# axiom_beta_plugin_module_3xPMOD_v1_2_22e.net
KiCad netlist of a schematic drawn in EAGLE
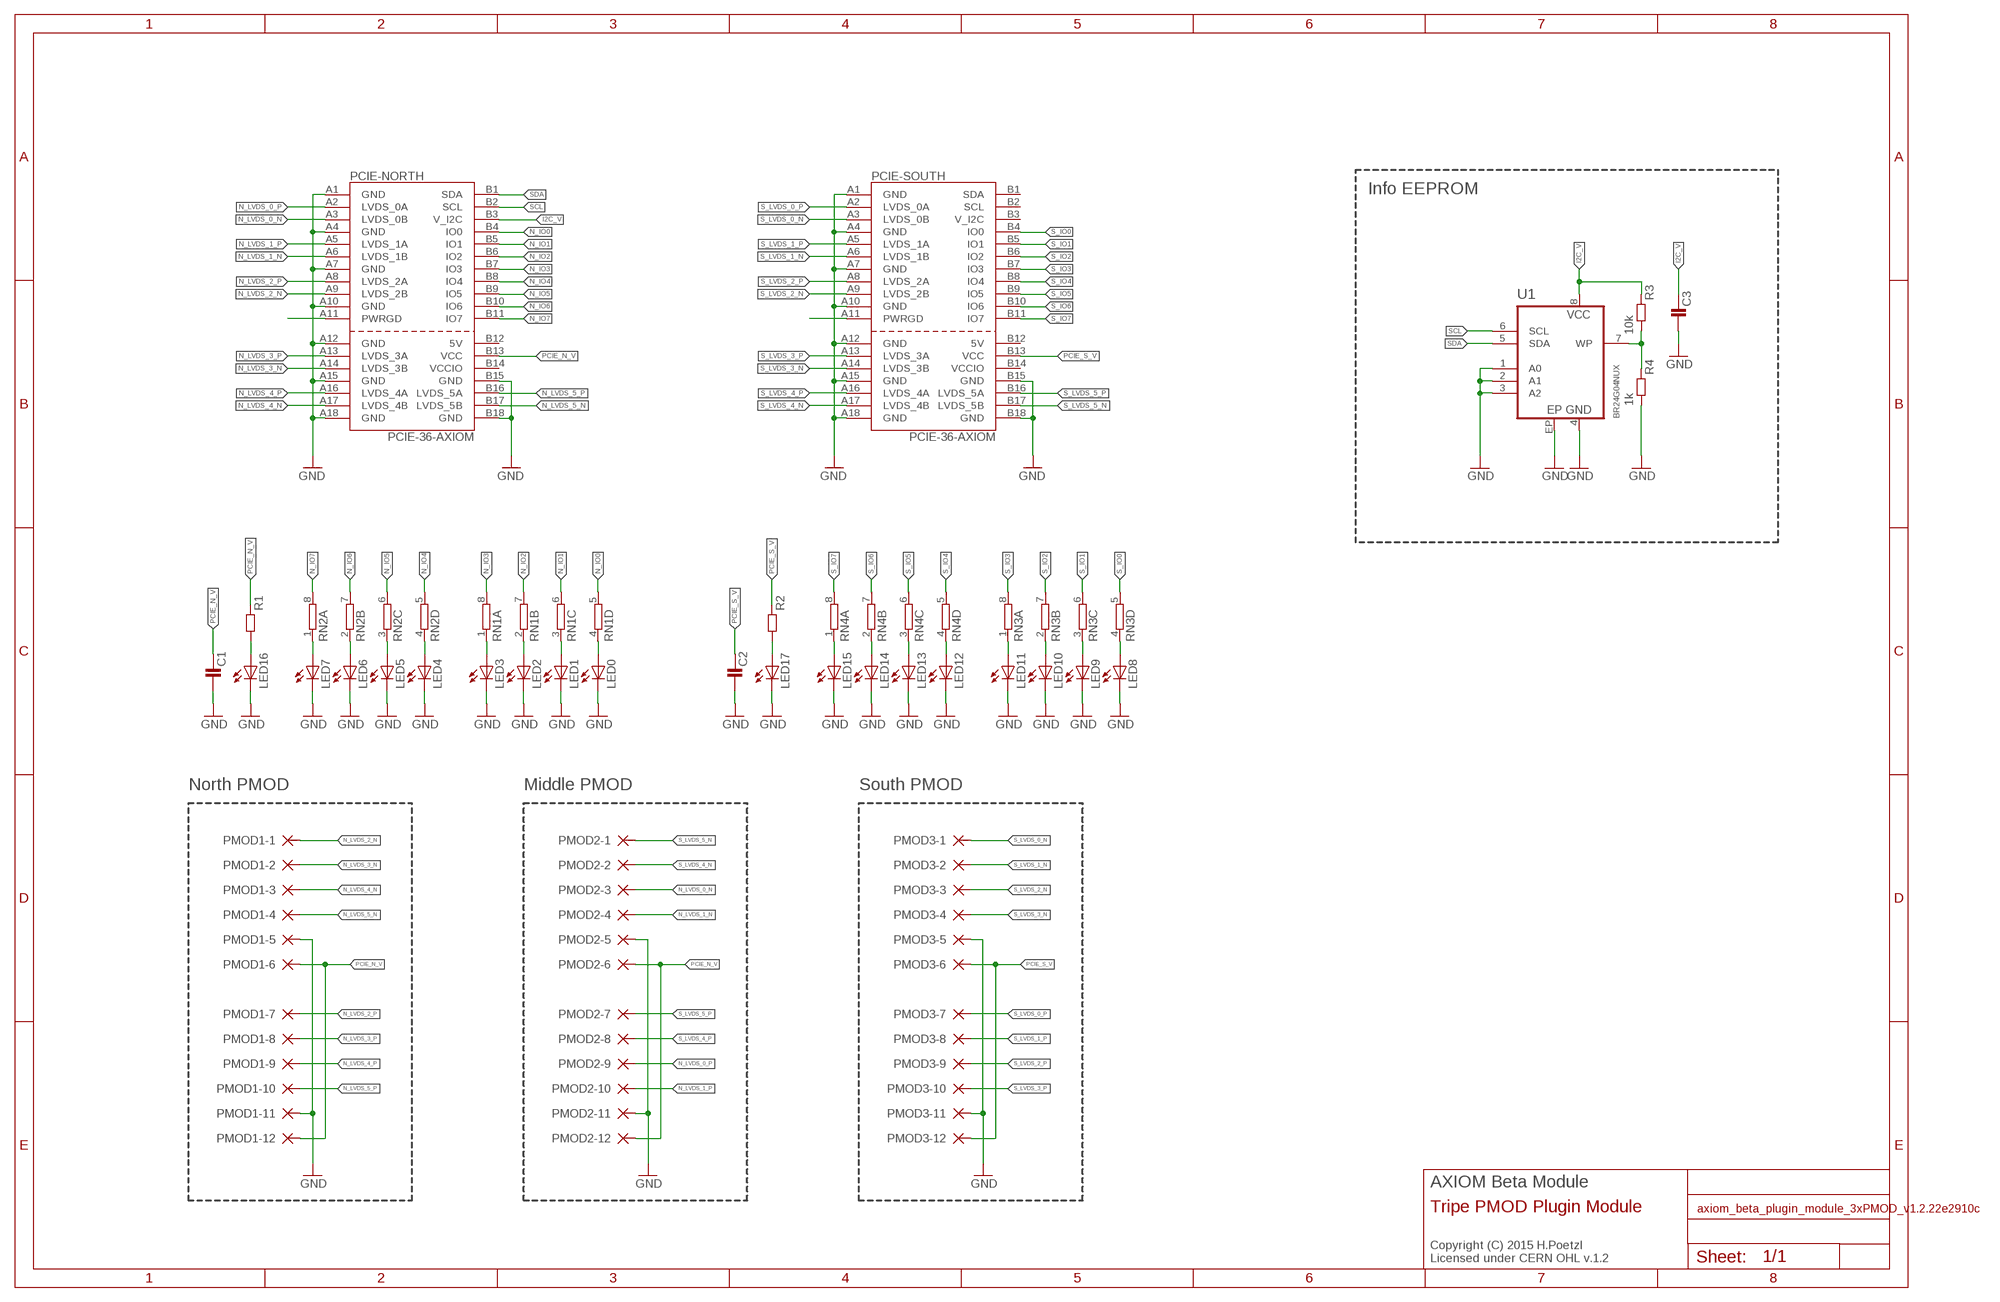
[diagram p0: schematic, sheet 1]

(export (version "E")
  (design (tool "Eeschema 10.0.6"))
  (components
    (comp (ref "C1")
      (value "C1206-A")
      (footprint "eagle-import:1206-A")
      (libsource (lib "eagle-import") (part "C1206-A"))
    )
    (comp (ref "C2")
      (value "C1206-A")
      (footprint "eagle-import:1206-A")
      (libsource (lib "eagle-import") (part "C1206-A"))
    )
    (comp (ref "C3")
      (value "C0402-B")
      (footprint "eagle-import:0402-B")
      (libsource (lib "eagle-import") (part "C0402-B"))
    )
    (comp (ref "LED0")
      (value "LEDCHIPLED_0603")
      (footprint "eagle-import:CHIPLED_0603")
      (libsource (lib "eagle-import") (part "LEDCHIPLED_0603"))
    )
    (comp (ref "LED1")
      (value "LEDCHIPLED_0603")
      (footprint "eagle-import:CHIPLED_0603")
      (libsource (lib "eagle-import") (part "LEDCHIPLED_0603"))
    )
    (comp (ref "LED2")
      (value "LEDCHIPLED_0603")
      (footprint "eagle-import:CHIPLED_0603")
      (libsource (lib "eagle-import") (part "LEDCHIPLED_0603"))
    )
    (comp (ref "LED3")
      (value "LEDCHIPLED_0603")
      (footprint "eagle-import:CHIPLED_0603")
      (libsource (lib "eagle-import") (part "LEDCHIPLED_0603"))
    )
    (comp (ref "LED4")
      (value "LEDCHIPLED_0603")
      (footprint "eagle-import:CHIPLED_0603")
      (libsource (lib "eagle-import") (part "LEDCHIPLED_0603"))
    )
    (comp (ref "LED5")
      (value "LEDCHIPLED_0603")
      (footprint "eagle-import:CHIPLED_0603")
      (libsource (lib "eagle-import") (part "LEDCHIPLED_0603"))
    )
    (comp (ref "LED6")
      (value "LEDCHIPLED_0603")
      (footprint "eagle-import:CHIPLED_0603")
      (libsource (lib "eagle-import") (part "LEDCHIPLED_0603"))
    )
    (comp (ref "LED7")
      (value "LEDCHIPLED_0603")
      (footprint "eagle-import:CHIPLED_0603")
      (libsource (lib "eagle-import") (part "LEDCHIPLED_0603"))
    )
    (comp (ref "LED8")
      (value "LEDCHIPLED_0603")
      (footprint "eagle-import:CHIPLED_0603")
      (libsource (lib "eagle-import") (part "LEDCHIPLED_0603"))
    )
    (comp (ref "LED9")
      (value "LEDCHIPLED_0603")
      (footprint "eagle-import:CHIPLED_0603")
      (libsource (lib "eagle-import") (part "LEDCHIPLED_0603"))
    )
    (comp (ref "LED10")
      (value "LEDCHIPLED_0603")
      (footprint "eagle-import:CHIPLED_0603")
      (libsource (lib "eagle-import") (part "LEDCHIPLED_0603"))
    )
    (comp (ref "LED11")
      (value "LEDCHIPLED_0603")
      (footprint "eagle-import:CHIPLED_0603")
      (libsource (lib "eagle-import") (part "LEDCHIPLED_0603"))
    )
    (comp (ref "LED12")
      (value "LEDCHIPLED_0603")
      (footprint "eagle-import:CHIPLED_0603")
      (libsource (lib "eagle-import") (part "LEDCHIPLED_0603"))
    )
    (comp (ref "LED13")
      (value "LEDCHIPLED_0603")
      (footprint "eagle-import:CHIPLED_0603")
      (libsource (lib "eagle-import") (part "LEDCHIPLED_0603"))
    )
    (comp (ref "LED14")
      (value "LEDCHIPLED_0603")
      (footprint "eagle-import:CHIPLED_0603")
      (libsource (lib "eagle-import") (part "LEDCHIPLED_0603"))
    )
    (comp (ref "LED15")
      (value "LEDCHIPLED_0603")
      (footprint "eagle-import:CHIPLED_0603")
      (libsource (lib "eagle-import") (part "LEDCHIPLED_0603"))
    )
    (comp (ref "LED16")
      (value "LEDCHIPLED_0603")
      (footprint "eagle-import:CHIPLED_0603")
      (libsource (lib "eagle-import") (part "LEDCHIPLED_0603"))
    )
    (comp (ref "LED17")
      (value "LEDCHIPLED_0603")
      (footprint "eagle-import:CHIPLED_0603")
      (libsource (lib "eagle-import") (part "LEDCHIPLED_0603"))
    )
    (comp (ref "PCIE-NORTH")
      (value "PCIE-36-AXIOM")
      (footprint "eagle-import:PCIE-36-AXIOM")
      (libsource (lib "eagle-import") (part "PCIE-36-AXIOM"))
    )
    (comp (ref "PCIE-SOUTH")
      (value "PCIE-36-AXIOM")
      (footprint "eagle-import:PCIE-36-AXIOM")
      (libsource (lib "eagle-import") (part "PCIE-36-AXIOM"))
    )
    (comp (ref "PMOD1-1")
      (value "SMD-PAD1.6X3.8MM-U")
      (footprint "eagle-import:1.6X3.8U-MM")
      (libsource (lib "eagle-import") (part "SMD-PAD1.6X3.8MM-U"))
    )
    (comp (ref "PMOD1-2")
      (value "SMD-PAD1.6X3.8MM-U")
      (footprint "eagle-import:1.6X3.8U-MM")
      (libsource (lib "eagle-import") (part "SMD-PAD1.6X3.8MM-U"))
    )
    (comp (ref "PMOD1-3")
      (value "SMD-PAD1.6X3.8MM-U")
      (footprint "eagle-import:1.6X3.8U-MM")
      (libsource (lib "eagle-import") (part "SMD-PAD1.6X3.8MM-U"))
    )
    (comp (ref "PMOD1-4")
      (value "SMD-PAD1.6X3.8MM-U")
      (footprint "eagle-import:1.6X3.8U-MM")
      (libsource (lib "eagle-import") (part "SMD-PAD1.6X3.8MM-U"))
    )
    (comp (ref "PMOD1-5")
      (value "SMD-PAD1.6X3.8MM-U")
      (footprint "eagle-import:1.6X3.8U-MM")
      (libsource (lib "eagle-import") (part "SMD-PAD1.6X3.8MM-U"))
    )
    (comp (ref "PMOD1-6")
      (value "SMD-PAD1.6X3.8MM-U")
      (footprint "eagle-import:1.6X3.8U-MM")
      (libsource (lib "eagle-import") (part "SMD-PAD1.6X3.8MM-U"))
    )
    (comp (ref "PMOD1-7")
      (value "SMD-PAD1.6X3.8MM-U")
      (footprint "eagle-import:1.6X3.8U-MM")
      (libsource (lib "eagle-import") (part "SMD-PAD1.6X3.8MM-U"))
    )
    (comp (ref "PMOD1-8")
      (value "SMD-PAD1.6X3.8MM-U")
      (footprint "eagle-import:1.6X3.8U-MM")
      (libsource (lib "eagle-import") (part "SMD-PAD1.6X3.8MM-U"))
    )
    (comp (ref "PMOD1-9")
      (value "SMD-PAD1.6X3.8MM-U")
      (footprint "eagle-import:1.6X3.8U-MM")
      (libsource (lib "eagle-import") (part "SMD-PAD1.6X3.8MM-U"))
    )
    (comp (ref "PMOD1-10")
      (value "SMD-PAD1.6X3.8MM-U")
      (footprint "eagle-import:1.6X3.8U-MM")
      (libsource (lib "eagle-import") (part "SMD-PAD1.6X3.8MM-U"))
    )
    (comp (ref "PMOD1-11")
      (value "SMD-PAD1.6X3.8MM-U")
      (footprint "eagle-import:1.6X3.8U-MM")
      (libsource (lib "eagle-import") (part "SMD-PAD1.6X3.8MM-U"))
    )
    (comp (ref "PMOD1-12")
      (value "SMD-PAD1.6X3.8MM-U")
      (footprint "eagle-import:1.6X3.8U-MM")
      (libsource (lib "eagle-import") (part "SMD-PAD1.6X3.8MM-U"))
    )
    (comp (ref "PMOD2-1")
      (value "SMD-PAD1.6X3.8MM-U")
      (footprint "eagle-import:1.6X3.8U-MM")
      (libsource (lib "eagle-import") (part "SMD-PAD1.6X3.8MM-U"))
    )
    (comp (ref "PMOD2-2")
      (value "SMD-PAD1.6X3.8MM-U")
      (footprint "eagle-import:1.6X3.8U-MM")
      (libsource (lib "eagle-import") (part "SMD-PAD1.6X3.8MM-U"))
    )
    (comp (ref "PMOD2-3")
      (value "SMD-PAD1.6X3.8MM-U")
      (footprint "eagle-import:1.6X3.8U-MM")
      (libsource (lib "eagle-import") (part "SMD-PAD1.6X3.8MM-U"))
    )
    (comp (ref "PMOD2-4")
      (value "SMD-PAD1.6X3.8MM-U")
      (footprint "eagle-import:1.6X3.8U-MM")
      (libsource (lib "eagle-import") (part "SMD-PAD1.6X3.8MM-U"))
    )
    (comp (ref "PMOD2-5")
      (value "SMD-PAD1.6X3.8MM-U")
      (footprint "eagle-import:1.6X3.8U-MM")
      (libsource (lib "eagle-import") (part "SMD-PAD1.6X3.8MM-U"))
    )
    (comp (ref "PMOD2-6")
      (value "SMD-PAD1.6X3.8MM-U")
      (footprint "eagle-import:1.6X3.8U-MM")
      (libsource (lib "eagle-import") (part "SMD-PAD1.6X3.8MM-U"))
    )
    (comp (ref "PMOD2-7")
      (value "SMD-PAD1.6X3.8MM-U")
      (footprint "eagle-import:1.6X3.8U-MM")
      (libsource (lib "eagle-import") (part "SMD-PAD1.6X3.8MM-U"))
    )
    (comp (ref "PMOD2-8")
      (value "SMD-PAD1.6X3.8MM-U")
      (footprint "eagle-import:1.6X3.8U-MM")
      (libsource (lib "eagle-import") (part "SMD-PAD1.6X3.8MM-U"))
    )
    (comp (ref "PMOD2-9")
      (value "SMD-PAD1.6X3.8MM-U")
      (footprint "eagle-import:1.6X3.8U-MM")
      (libsource (lib "eagle-import") (part "SMD-PAD1.6X3.8MM-U"))
    )
    (comp (ref "PMOD2-10")
      (value "SMD-PAD1.6X3.8MM-U")
      (footprint "eagle-import:1.6X3.8U-MM")
      (libsource (lib "eagle-import") (part "SMD-PAD1.6X3.8MM-U"))
    )
    (comp (ref "PMOD2-11")
      (value "SMD-PAD1.6X3.8MM-U")
      (footprint "eagle-import:1.6X3.8U-MM")
      (libsource (lib "eagle-import") (part "SMD-PAD1.6X3.8MM-U"))
    )
    (comp (ref "PMOD2-12")
      (value "SMD-PAD1.6X3.8MM-U")
      (footprint "eagle-import:1.6X3.8U-MM")
      (libsource (lib "eagle-import") (part "SMD-PAD1.6X3.8MM-U"))
    )
    (comp (ref "PMOD3-1")
      (value "SMD-PAD1.6X3.8MM-U")
      (footprint "eagle-import:1.6X3.8U-MM")
      (libsource (lib "eagle-import") (part "SMD-PAD1.6X3.8MM-U"))
    )
    (comp (ref "PMOD3-2")
      (value "SMD-PAD1.6X3.8MM-U")
      (footprint "eagle-import:1.6X3.8U-MM")
      (libsource (lib "eagle-import") (part "SMD-PAD1.6X3.8MM-U"))
    )
    (comp (ref "PMOD3-3")
      (value "SMD-PAD1.6X3.8MM-U")
      (footprint "eagle-import:1.6X3.8U-MM")
      (libsource (lib "eagle-import") (part "SMD-PAD1.6X3.8MM-U"))
    )
    (comp (ref "PMOD3-4")
      (value "SMD-PAD1.6X3.8MM-U")
      (footprint "eagle-import:1.6X3.8U-MM")
      (libsource (lib "eagle-import") (part "SMD-PAD1.6X3.8MM-U"))
    )
    (comp (ref "PMOD3-5")
      (value "SMD-PAD1.6X3.8MM-U")
      (footprint "eagle-import:1.6X3.8U-MM")
      (libsource (lib "eagle-import") (part "SMD-PAD1.6X3.8MM-U"))
    )
    (comp (ref "PMOD3-6")
      (value "SMD-PAD1.6X3.8MM-U")
      (footprint "eagle-import:1.6X3.8U-MM")
      (libsource (lib "eagle-import") (part "SMD-PAD1.6X3.8MM-U"))
    )
    (comp (ref "PMOD3-7")
      (value "SMD-PAD1.6X3.8MM-U")
      (footprint "eagle-import:1.6X3.8U-MM")
      (libsource (lib "eagle-import") (part "SMD-PAD1.6X3.8MM-U"))
    )
    (comp (ref "PMOD3-8")
      (value "SMD-PAD1.6X3.8MM-U")
      (footprint "eagle-import:1.6X3.8U-MM")
      (libsource (lib "eagle-import") (part "SMD-PAD1.6X3.8MM-U"))
    )
    (comp (ref "PMOD3-9")
      (value "SMD-PAD1.6X3.8MM-U")
      (footprint "eagle-import:1.6X3.8U-MM")
      (libsource (lib "eagle-import") (part "SMD-PAD1.6X3.8MM-U"))
    )
    (comp (ref "PMOD3-10")
      (value "SMD-PAD1.6X3.8MM-U")
      (footprint "eagle-import:1.6X3.8U-MM")
      (libsource (lib "eagle-import") (part "SMD-PAD1.6X3.8MM-U"))
    )
    (comp (ref "PMOD3-11")
      (value "SMD-PAD1.6X3.8MM-U")
      (footprint "eagle-import:1.6X3.8U-MM")
      (libsource (lib "eagle-import") (part "SMD-PAD1.6X3.8MM-U"))
    )
    (comp (ref "PMOD3-12")
      (value "SMD-PAD1.6X3.8MM-U")
      (footprint "eagle-import:1.6X3.8U-MM")
      (libsource (lib "eagle-import") (part "SMD-PAD1.6X3.8MM-U"))
    )
    (comp (ref "R1")
      (value "R0402-B")
      (footprint "eagle-import:0402-B")
      (libsource (lib "eagle-import") (part "R0402-B"))
    )
    (comp (ref "R2")
      (value "R0402-B")
      (footprint "eagle-import:0402-B")
      (libsource (lib "eagle-import") (part "R0402-B"))
    )
    (comp (ref "R3")
      (value "10k")
      (footprint "eagle-import:0402-B")
      (libsource (lib "eagle-import") (part "R0402-B"))
    )
    (comp (ref "R4")
      (value "1k")
      (footprint "eagle-import:0402-B")
      (libsource (lib "eagle-import") (part "R0402-B"))
    )
    (comp (ref "RN1")
      (value "4R-NCAY16")
      (footprint "eagle-import:CAY16")
      (libsource (lib "eagle-import") (part "4R-NCAY16"))
    )
    (comp (ref "RN2")
      (value "4R-NCAY16")
      (footprint "eagle-import:CAY16")
      (libsource (lib "eagle-import") (part "4R-NCAY16"))
    )
    (comp (ref "RN3")
      (value "4R-NCAY16")
      (footprint "eagle-import:CAY16")
      (libsource (lib "eagle-import") (part "4R-NCAY16"))
    )
    (comp (ref "RN4")
      (value "4R-NCAY16")
      (footprint "eagle-import:CAY16")
      (libsource (lib "eagle-import") (part "4R-NCAY16"))
    )
    (comp (ref "U1")
      (value "BR24G04NUX")
      (footprint "eagle-import:DFN200X300X100-9N")
      (libsource (lib "eagle-import") (part "BR24G04NUX"))
    )
  )
  (nets
    (net (code "1") (name "GND") (class "Default")
      (node (ref "C1") (pin "2") (pinfunction "2_2") (pintype "passive"))
      (node (ref "C2") (pin "2") (pinfunction "2_2") (pintype "passive"))
      (node (ref "C3") (pin "2") (pinfunction "2_2") (pintype "passive"))
      (node (ref "LED0") (pin "C") (pinfunction "C_C") (pintype "passive"))
      (node (ref "LED1") (pin "C") (pinfunction "C_C") (pintype "passive"))
      (node (ref "LED10") (pin "C") (pinfunction "C_C") (pintype "passive"))
      (node (ref "LED11") (pin "C") (pinfunction "C_C") (pintype "passive"))
      (node (ref "LED12") (pin "C") (pinfunction "C_C") (pintype "passive"))
      (node (ref "LED13") (pin "C") (pinfunction "C_C") (pintype "passive"))
      (node (ref "LED14") (pin "C") (pinfunction "C_C") (pintype "passive"))
      (node (ref "LED15") (pin "C") (pinfunction "C_C") (pintype "passive"))
      (node (ref "LED16") (pin "C") (pinfunction "C_C") (pintype "passive"))
      (node (ref "LED17") (pin "C") (pinfunction "C_C") (pintype "passive"))
      (node (ref "LED2") (pin "C") (pinfunction "C_C") (pintype "passive"))
      (node (ref "LED3") (pin "C") (pinfunction "C_C") (pintype "passive"))
      (node (ref "LED4") (pin "C") (pinfunction "C_C") (pintype "passive"))
      (node (ref "LED5") (pin "C") (pinfunction "C_C") (pintype "passive"))
      (node (ref "LED6") (pin "C") (pinfunction "C_C") (pintype "passive"))
      (node (ref "LED7") (pin "C") (pinfunction "C_C") (pintype "passive"))
      (node (ref "LED8") (pin "C") (pinfunction "C_C") (pintype "passive"))
      (node (ref "LED9") (pin "C") (pinfunction "C_C") (pintype "passive"))
      (node (ref "PCIE-NORTH") (pin "A1") (pinfunction "GND_A1") (pintype "passive"))
      (node (ref "PCIE-NORTH") (pin "A10") (pinfunction "GND_A10") (pintype "passive"))
      (node (ref "PCIE-NORTH") (pin "A12") (pinfunction "GND_A12") (pintype "passive"))
      (node (ref "PCIE-NORTH") (pin "A15") (pinfunction "GND_A15") (pintype "passive"))
      (node (ref "PCIE-NORTH") (pin "A18") (pinfunction "GND_A18") (pintype "passive"))
      (node (ref "PCIE-NORTH") (pin "A4") (pinfunction "GND_A4") (pintype "passive"))
      (node (ref "PCIE-NORTH") (pin "A7") (pinfunction "GND_A7") (pintype "passive"))
      (node (ref "PCIE-NORTH") (pin "B15") (pinfunction "GND_B15") (pintype "passive"))
      (node (ref "PCIE-NORTH") (pin "B18") (pinfunction "GND_B18") (pintype "passive"))
      (node (ref "PCIE-SOUTH") (pin "A1") (pinfunction "GND_A1") (pintype "passive"))
      (node (ref "PCIE-SOUTH") (pin "A10") (pinfunction "GND_A10") (pintype "passive"))
      (node (ref "PCIE-SOUTH") (pin "A12") (pinfunction "GND_A12") (pintype "passive"))
      (node (ref "PCIE-SOUTH") (pin "A15") (pinfunction "GND_A15") (pintype "passive"))
      (node (ref "PCIE-SOUTH") (pin "A18") (pinfunction "GND_A18") (pintype "passive"))
      (node (ref "PCIE-SOUTH") (pin "A4") (pinfunction "GND_A4") (pintype "passive"))
      (node (ref "PCIE-SOUTH") (pin "A7") (pinfunction "GND_A7") (pintype "passive"))
      (node (ref "PCIE-SOUTH") (pin "B15") (pinfunction "GND_B15") (pintype "passive"))
      (node (ref "PCIE-SOUTH") (pin "B18") (pinfunction "GND_B18") (pintype "passive"))
      (node (ref "PMOD1-11") (pin "1") (pinfunction "P_1") (pintype "passive"))
      (node (ref "PMOD1-5") (pin "1") (pinfunction "P_1") (pintype "passive"))
      (node (ref "PMOD2-11") (pin "1") (pinfunction "P_1") (pintype "passive"))
      (node (ref "PMOD2-5") (pin "1") (pinfunction "P_1") (pintype "passive"))
      (node (ref "PMOD3-11") (pin "1") (pinfunction "P_1") (pintype "passive"))
      (node (ref "PMOD3-5") (pin "1") (pinfunction "P_1") (pintype "passive"))
      (node (ref "R4") (pin "2") (pinfunction "2_2") (pintype "passive"))
      (node (ref "U1") (pin "1") (pinfunction "A0_1") (pintype "input"))
      (node (ref "U1") (pin "2") (pinfunction "A1_2") (pintype "input"))
      (node (ref "U1") (pin "3") (pinfunction "A2_3") (pintype "input"))
      (node (ref "U1") (pin "4") (pinfunction "GND_4") (pintype "passive"))
      (node (ref "U1") (pin "EP") (pinfunction "EP_EP") (pintype "passive"))
    )
    (net (code "2") (name "I2C_V") (class "Default")
      (node (ref "C3") (pin "1") (pinfunction "1_1") (pintype "passive"))
      (node (ref "PCIE-NORTH") (pin "B3") (pinfunction "V_I2C_B3") (pintype "passive"))
      (node (ref "R3") (pin "1") (pinfunction "1_1") (pintype "passive"))
      (node (ref "U1") (pin "8") (pinfunction "VCC_8") (pintype "power_in"))
    )
    (net (code "3") (name "N_IO0") (class "Default")
      (node (ref "PCIE-NORTH") (pin "B4") (pinfunction "IO0_B4") (pintype "passive"))
      (node (ref "RN1") (pin "5") (pinfunction "2_5") (pintype "passive"))
    )
    (net (code "4") (name "N_IO1") (class "Default")
      (node (ref "PCIE-NORTH") (pin "B5") (pinfunction "IO1_B5") (pintype "passive"))
      (node (ref "RN1") (pin "6") (pinfunction "2_6") (pintype "passive"))
    )
    (net (code "5") (name "N_IO2") (class "Default")
      (node (ref "PCIE-NORTH") (pin "B6") (pinfunction "IO2_B6") (pintype "passive"))
      (node (ref "RN1") (pin "7") (pinfunction "2_7") (pintype "passive"))
    )
    (net (code "6") (name "N_IO3") (class "Default")
      (node (ref "PCIE-NORTH") (pin "B7") (pinfunction "IO3_B7") (pintype "passive"))
      (node (ref "RN1") (pin "8") (pinfunction "2_8") (pintype "passive"))
    )
    (net (code "7") (name "N_IO4") (class "Default")
      (node (ref "PCIE-NORTH") (pin "B8") (pinfunction "IO4_B8") (pintype "passive"))
      (node (ref "RN2") (pin "5") (pinfunction "2_5") (pintype "passive"))
    )
    (net (code "8") (name "N_IO5") (class "Default")
      (node (ref "PCIE-NORTH") (pin "B9") (pinfunction "IO5_B9") (pintype "passive"))
      (node (ref "RN2") (pin "6") (pinfunction "2_6") (pintype "passive"))
    )
    (net (code "9") (name "N_IO6") (class "Default")
      (node (ref "PCIE-NORTH") (pin "B10") (pinfunction "IO6_B10") (pintype "passive"))
      (node (ref "RN2") (pin "7") (pinfunction "2_7") (pintype "passive"))
    )
    (net (code "10") (name "N_IO7") (class "Default")
      (node (ref "PCIE-NORTH") (pin "B11") (pinfunction "IO7_B11") (pintype "passive"))
      (node (ref "RN2") (pin "8") (pinfunction "2_8") (pintype "passive"))
    )
    (net (code "11") (name "N_LVDS_0_N") (class "Default")
      (node (ref "PCIE-NORTH") (pin "A3") (pinfunction "LVDS_0B_A3") (pintype "passive"))
      (node (ref "PMOD2-3") (pin "1") (pinfunction "P_1") (pintype "passive"))
    )
    (net (code "12") (name "N_LVDS_0_P") (class "Default")
      (node (ref "PCIE-NORTH") (pin "A2") (pinfunction "LVDS_0A_A2") (pintype "passive"))
      (node (ref "PMOD2-9") (pin "1") (pinfunction "P_1") (pintype "passive"))
    )
    (net (code "13") (name "N_LVDS_1_N") (class "Default")
      (node (ref "PCIE-NORTH") (pin "A6") (pinfunction "LVDS_1B_A6") (pintype "passive"))
      (node (ref "PMOD2-4") (pin "1") (pinfunction "P_1") (pintype "passive"))
    )
    (net (code "14") (name "N_LVDS_1_P") (class "Default")
      (node (ref "PCIE-NORTH") (pin "A5") (pinfunction "LVDS_1A_A5") (pintype "passive"))
      (node (ref "PMOD2-10") (pin "1") (pinfunction "P_1") (pintype "passive"))
    )
    (net (code "15") (name "N_LVDS_2_N") (class "Default")
      (node (ref "PCIE-NORTH") (pin "A9") (pinfunction "LVDS_2B_A9") (pintype "passive"))
      (node (ref "PMOD1-1") (pin "1") (pinfunction "P_1") (pintype "passive"))
    )
    (net (code "16") (name "N_LVDS_2_P") (class "Default")
      (node (ref "PCIE-NORTH") (pin "A8") (pinfunction "LVDS_2A_A8") (pintype "passive"))
      (node (ref "PMOD1-7") (pin "1") (pinfunction "P_1") (pintype "passive"))
    )
    (net (code "17") (name "N_LVDS_3_N") (class "Default")
      (node (ref "PCIE-NORTH") (pin "A14") (pinfunction "LVDS_3B_A14") (pintype "passive"))
      (node (ref "PMOD1-2") (pin "1") (pinfunction "P_1") (pintype "passive"))
    )
    (net (code "18") (name "N_LVDS_3_P") (class "Default")
      (node (ref "PCIE-NORTH") (pin "A13") (pinfunction "LVDS_3A_A13") (pintype "passive"))
      (node (ref "PMOD1-8") (pin "1") (pinfunction "P_1") (pintype "passive"))
    )
    (net (code "19") (name "N_LVDS_4_N") (class "Default")
      (node (ref "PCIE-NORTH") (pin "A17") (pinfunction "LVDS_4B_A17") (pintype "passive"))
      (node (ref "PMOD1-3") (pin "1") (pinfunction "P_1") (pintype "passive"))
    )
    (net (code "20") (name "N_LVDS_4_P") (class "Default")
      (node (ref "PCIE-NORTH") (pin "A16") (pinfunction "LVDS_4A_A16") (pintype "passive"))
      (node (ref "PMOD1-9") (pin "1") (pinfunction "P_1") (pintype "passive"))
    )
    (net (code "21") (name "N_LVDS_5_N") (class "Default")
      (node (ref "PCIE-NORTH") (pin "B17") (pinfunction "LVDS_5B_B17") (pintype "passive"))
      (node (ref "PMOD1-4") (pin "1") (pinfunction "P_1") (pintype "passive"))
    )
    (net (code "22") (name "N_LVDS_5_P") (class "Default")
      (node (ref "PCIE-NORTH") (pin "B16") (pinfunction "LVDS_5A_B16") (pintype "passive"))
      (node (ref "PMOD1-10") (pin "1") (pinfunction "P_1") (pintype "passive"))
    )
    (net (code "23") (name "Net-(LED3-PadA)") (class "Default")
      (node (ref "LED3") (pin "A") (pinfunction "A_A") (pintype "passive"))
      (node (ref "RN1") (pin "1") (pinfunction "1_1") (pintype "passive"))
    )
    (net (code "24") (name "Net-(LED7-PadA)") (class "Default")
      (node (ref "LED7") (pin "A") (pinfunction "A_A") (pintype "passive"))
      (node (ref "RN2") (pin "1") (pinfunction "1_1") (pintype "passive"))
    )
    (net (code "25") (name "Net-(LED11-PadA)") (class "Default")
      (node (ref "LED11") (pin "A") (pinfunction "A_A") (pintype "passive"))
      (node (ref "RN3") (pin "1") (pinfunction "1_1") (pintype "passive"))
    )
    (net (code "26") (name "Net-(LED15-PadA)") (class "Default")
      (node (ref "LED15") (pin "A") (pinfunction "A_A") (pintype "passive"))
      (node (ref "RN4") (pin "1") (pinfunction "1_1") (pintype "passive"))
    )
    (net (code "27") (name "Net-(LED16-PadA)") (class "Default")
      (node (ref "LED16") (pin "A") (pinfunction "A_A") (pintype "passive"))
      (node (ref "R1") (pin "2") (pinfunction "2_2") (pintype "passive"))
    )
    (net (code "28") (name "Net-(LED17-PadA)") (class "Default")
      (node (ref "LED17") (pin "A") (pinfunction "A_A") (pintype "passive"))
      (node (ref "R2") (pin "2") (pinfunction "2_2") (pintype "passive"))
    )
    (net (code "29") (name "Net-(RN1B-1)") (class "Default")
      (node (ref "LED2") (pin "A") (pinfunction "A_A") (pintype "passive"))
      (node (ref "RN1") (pin "2") (pinfunction "1_2") (pintype "passive"))
    )
    (net (code "30") (name "Net-(RN1C-1)") (class "Default")
      (node (ref "LED1") (pin "A") (pinfunction "A_A") (pintype "passive"))
      (node (ref "RN1") (pin "3") (pinfunction "1_3") (pintype "passive"))
    )
    (net (code "31") (name "Net-(RN1D-1)") (class "Default")
      (node (ref "LED0") (pin "A") (pinfunction "A_A") (pintype "passive"))
      (node (ref "RN1") (pin "4") (pinfunction "1_4") (pintype "passive"))
    )
    (net (code "32") (name "Net-(RN2B-1)") (class "Default")
      (node (ref "LED6") (pin "A") (pinfunction "A_A") (pintype "passive"))
      (node (ref "RN2") (pin "2") (pinfunction "1_2") (pintype "passive"))
    )
    (net (code "33") (name "Net-(RN2C-1)") (class "Default")
      (node (ref "LED5") (pin "A") (pinfunction "A_A") (pintype "passive"))
      (node (ref "RN2") (pin "3") (pinfunction "1_3") (pintype "passive"))
    )
    (net (code "34") (name "Net-(RN2D-1)") (class "Default")
      (node (ref "LED4") (pin "A") (pinfunction "A_A") (pintype "passive"))
      (node (ref "RN2") (pin "4") (pinfunction "1_4") (pintype "passive"))
    )
    (net (code "35") (name "Net-(RN3B-1)") (class "Default")
      (node (ref "LED10") (pin "A") (pinfunction "A_A") (pintype "passive"))
      (node (ref "RN3") (pin "2") (pinfunction "1_2") (pintype "passive"))
    )
    (net (code "36") (name "Net-(RN3C-1)") (class "Default")
      (node (ref "LED9") (pin "A") (pinfunction "A_A") (pintype "passive"))
      (node (ref "RN3") (pin "3") (pinfunction "1_3") (pintype "passive"))
    )
    (net (code "37") (name "Net-(RN3D-1)") (class "Default")
      (node (ref "LED8") (pin "A") (pinfunction "A_A") (pintype "passive"))
      (node (ref "RN3") (pin "4") (pinfunction "1_4") (pintype "passive"))
    )
    (net (code "38") (name "Net-(RN4B-1)") (class "Default")
      (node (ref "LED14") (pin "A") (pinfunction "A_A") (pintype "passive"))
      (node (ref "RN4") (pin "2") (pinfunction "1_2") (pintype "passive"))
    )
    (net (code "39") (name "Net-(RN4C-1)") (class "Default")
      (node (ref "LED13") (pin "A") (pinfunction "A_A") (pintype "passive"))
      (node (ref "RN4") (pin "3") (pinfunction "1_3") (pintype "passive"))
    )
    (net (code "40") (name "Net-(RN4D-1)") (class "Default")
      (node (ref "LED12") (pin "A") (pinfunction "A_A") (pintype "passive"))
      (node (ref "RN4") (pin "4") (pinfunction "1_4") (pintype "passive"))
    )
    (net (code "41") (name "Net-(U1-WP)") (class "Default")
      (node (ref "R3") (pin "2") (pinfunction "2_2") (pintype "passive"))
      (node (ref "R4") (pin "1") (pinfunction "1_1") (pintype "passive"))
      (node (ref "U1") (pin "7") (pinfunction "WP_7") (pintype "input"))
    )
    (net (code "42") (name "PCIE_N_V") (class "Default")
      (node (ref "C1") (pin "1") (pinfunction "1_1") (pintype "passive"))
      (node (ref "PCIE-NORTH") (pin "B13") (pinfunction "VCC_B13") (pintype "passive"))
      (node (ref "PMOD1-12") (pin "1") (pinfunction "P_1") (pintype "passive"))
      (node (ref "PMOD1-6") (pin "1") (pinfunction "P_1") (pintype "passive"))
      (node (ref "PMOD2-12") (pin "1") (pinfunction "P_1") (pintype "passive"))
      (node (ref "PMOD2-6") (pin "1") (pinfunction "P_1") (pintype "passive"))
      (node (ref "R1") (pin "1") (pinfunction "1_1") (pintype "passive"))
    )
    (net (code "43") (name "PCIE_S_V") (class "Default")
      (node (ref "C2") (pin "1") (pinfunction "1_1") (pintype "passive"))
      (node (ref "PCIE-SOUTH") (pin "B13") (pinfunction "VCC_B13") (pintype "passive"))
      (node (ref "PMOD3-12") (pin "1") (pinfunction "P_1") (pintype "passive"))
      (node (ref "PMOD3-6") (pin "1") (pinfunction "P_1") (pintype "passive"))
      (node (ref "R2") (pin "1") (pinfunction "1_1") (pintype "passive"))
    )
    (net (code "44") (name "SCL") (class "Default")
      (node (ref "PCIE-NORTH") (pin "B2") (pinfunction "SCL_B2") (pintype "passive"))
      (node (ref "U1") (pin "6") (pinfunction "SCL_6") (pintype "input"))
    )
    (net (code "45") (name "SDA") (class "Default")
      (node (ref "PCIE-NORTH") (pin "B1") (pinfunction "SDA_B1") (pintype "passive"))
      (node (ref "U1") (pin "5") (pinfunction "SDA_5") (pintype "bidirectional"))
    )
    (net (code "46") (name "S_IO0") (class "Default")
      (node (ref "PCIE-SOUTH") (pin "B4") (pinfunction "IO0_B4") (pintype "passive"))
      (node (ref "RN3") (pin "5") (pinfunction "2_5") (pintype "passive"))
    )
    (net (code "47") (name "S_IO1") (class "Default")
      (node (ref "PCIE-SOUTH") (pin "B5") (pinfunction "IO1_B5") (pintype "passive"))
      (node (ref "RN3") (pin "6") (pinfunction "2_6") (pintype "passive"))
    )
    (net (code "48") (name "S_IO2") (class "Default")
      (node (ref "PCIE-SOUTH") (pin "B6") (pinfunction "IO2_B6") (pintype "passive"))
      (node (ref "RN3") (pin "7") (pinfunction "2_7") (pintype "passive"))
    )
    (net (code "49") (name "S_IO3") (class "Default")
      (node (ref "PCIE-SOUTH") (pin "B7") (pinfunction "IO3_B7") (pintype "passive"))
      (node (ref "RN3") (pin "8") (pinfunction "2_8") (pintype "passive"))
    )
    (net (code "50") (name "S_IO4") (class "Default")
      (node (ref "PCIE-SOUTH") (pin "B8") (pinfunction "IO4_B8") (pintype "passive"))
      (node (ref "RN4") (pin "5") (pinfunction "2_5") (pintype "passive"))
    )
    (net (code "51") (name "S_IO5") (class "Default")
      (node (ref "PCIE-SOUTH") (pin "B9") (pinfunction "IO5_B9") (pintype "passive"))
      (node (ref "RN4") (pin "6") (pinfunction "2_6") (pintype "passive"))
    )
    (net (code "52") (name "S_IO6") (class "Default")
      (node (ref "PCIE-SOUTH") (pin "B10") (pinfunction "IO6_B10") (pintype "passive"))
      (node (ref "RN4") (pin "7") (pinfunction "2_7") (pintype "passive"))
    )
    (net (code "53") (name "S_IO7") (class "Default")
      (node (ref "PCIE-SOUTH") (pin "B11") (pinfunction "IO7_B11") (pintype "passive"))
      (node (ref "RN4") (pin "8") (pinfunction "2_8") (pintype "passive"))
    )
    (net (code "54") (name "S_LVDS_0_N") (class "Default")
      (node (ref "PCIE-SOUTH") (pin "A3") (pinfunction "LVDS_0B_A3") (pintype "passive"))
      (node (ref "PMOD3-1") (pin "1") (pinfunction "P_1") (pintype "passive"))
    )
    (net (code "55") (name "S_LVDS_0_P") (class "Default")
      (node (ref "PCIE-SOUTH") (pin "A2") (pinfunction "LVDS_0A_A2") (pintype "passive"))
      (node (ref "PMOD3-7") (pin "1") (pinfunction "P_1") (pintype "passive"))
    )
    (net (code "56") (name "S_LVDS_1_N") (class "Default")
      (node (ref "PCIE-SOUTH") (pin "A6") (pinfunction "LVDS_1B_A6") (pintype "passive"))
      (node (ref "PMOD3-2") (pin "1") (pinfunction "P_1") (pintype "passive"))
    )
    (net (code "57") (name "S_LVDS_1_P") (class "Default")
      (node (ref "PCIE-SOUTH") (pin "A5") (pinfunction "LVDS_1A_A5") (pintype "passive"))
      (node (ref "PMOD3-8") (pin "1") (pinfunction "P_1") (pintype "passive"))
    )
    (net (code "58") (name "S_LVDS_2_N") (class "Default")
      (node (ref "PCIE-SOUTH") (pin "A9") (pinfunction "LVDS_2B_A9") (pintype "passive"))
      (node (ref "PMOD3-3") (pin "1") (pinfunction "P_1") (pintype "passive"))
    )
    (net (code "59") (name "S_LVDS_2_P") (class "Default")
      (node (ref "PCIE-SOUTH") (pin "A8") (pinfunction "LVDS_2A_A8") (pintype "passive"))
      (node (ref "PMOD3-9") (pin "1") (pinfunction "P_1") (pintype "passive"))
    )
    (net (code "60") (name "S_LVDS_3_N") (class "Default")
      (node (ref "PCIE-SOUTH") (pin "A14") (pinfunction "LVDS_3B_A14") (pintype "passive"))
      (node (ref "PMOD3-4") (pin "1") (pinfunction "P_1") (pintype "passive"))
    )
    (net (code "61") (name "S_LVDS_3_P") (class "Default")
      (node (ref "PCIE-SOUTH") (pin "A13") (pinfunction "LVDS_3A_A13") (pintype "passive"))
      (node (ref "PMOD3-10") (pin "1") (pinfunction "P_1") (pintype "passive"))
    )
    (net (code "62") (name "S_LVDS_4_N") (class "Default")
      (node (ref "PCIE-SOUTH") (pin "A17") (pinfunction "LVDS_4B_A17") (pintype "passive"))
      (node (ref "PMOD2-2") (pin "1") (pinfunction "P_1") (pintype "passive"))
    )
    (net (code "63") (name "S_LVDS_4_P") (class "Default")
      (node (ref "PCIE-SOUTH") (pin "A16") (pinfunction "LVDS_4A_A16") (pintype "passive"))
      (node (ref "PMOD2-8") (pin "1") (pinfunction "P_1") (pintype "passive"))
    )
    (net (code "64") (name "S_LVDS_5_N") (class "Default")
      (node (ref "PCIE-SOUTH") (pin "B17") (pinfunction "LVDS_5B_B17") (pintype "passive"))
      (node (ref "PMOD2-1") (pin "1") (pinfunction "P_1") (pintype "passive"))
    )
    (net (code "65") (name "S_LVDS_5_P") (class "Default")
      (node (ref "PCIE-SOUTH") (pin "B16") (pinfunction "LVDS_5A_B16") (pintype "passive"))
      (node (ref "PMOD2-7") (pin "1") (pinfunction "P_1") (pintype "passive"))
    )
    (net (code "66") (name "unconnected-(PCIE-NORTH-5V-PadB12)") (class "Default")
      (node (ref "PCIE-NORTH") (pin "B12") (pinfunction "5V_B12") (pintype "passive"))
    )
    (net (code "67") (name "unconnected-(PCIE-NORTH-PWRGD-PadA11)") (class "Default")
      (node (ref "PCIE-NORTH") (pin "A11") (pinfunction "PWRGD_A11") (pintype "passive"))
    )
    (net (code "68") (name "unconnected-(PCIE-NORTH-VCCIO-PadB14)") (class "Default")
      (node (ref "PCIE-NORTH") (pin "B14") (pinfunction "VCCIO_B14") (pintype "passive"))
    )
    (net (code "69") (name "unconnected-(PCIE-SOUTH-5V-PadB12)") (class "Default")
      (node (ref "PCIE-SOUTH") (pin "B12") (pinfunction "5V_B12") (pintype "passive"))
    )
    (net (code "70") (name "unconnected-(PCIE-SOUTH-PWRGD-PadA11)") (class "Default")
      (node (ref "PCIE-SOUTH") (pin "A11") (pinfunction "PWRGD_A11") (pintype "passive"))
    )
    (net (code "71") (name "unconnected-(PCIE-SOUTH-SCL-PadB2)") (class "Default")
      (node (ref "PCIE-SOUTH") (pin "B2") (pinfunction "SCL_B2") (pintype "passive"))
    )
    (net (code "72") (name "unconnected-(PCIE-SOUTH-SDA-PadB1)") (class "Default")
      (node (ref "PCIE-SOUTH") (pin "B1") (pinfunction "SDA_B1") (pintype "passive"))
    )
    (net (code "73") (name "unconnected-(PCIE-SOUTH-VCCIO-PadB14)") (class "Default")
      (node (ref "PCIE-SOUTH") (pin "B14") (pinfunction "VCCIO_B14") (pintype "passive"))
    )
    (net (code "74") (name "unconnected-(PCIE-SOUTH-V_I2C-PadB3)") (class "Default")
      (node (ref "PCIE-SOUTH") (pin "B3") (pinfunction "V_I2C_B3") (pintype "passive"))
    )
  )
)
